# untitled.net
KiCad netlist of a schematic drawn in EAGLE
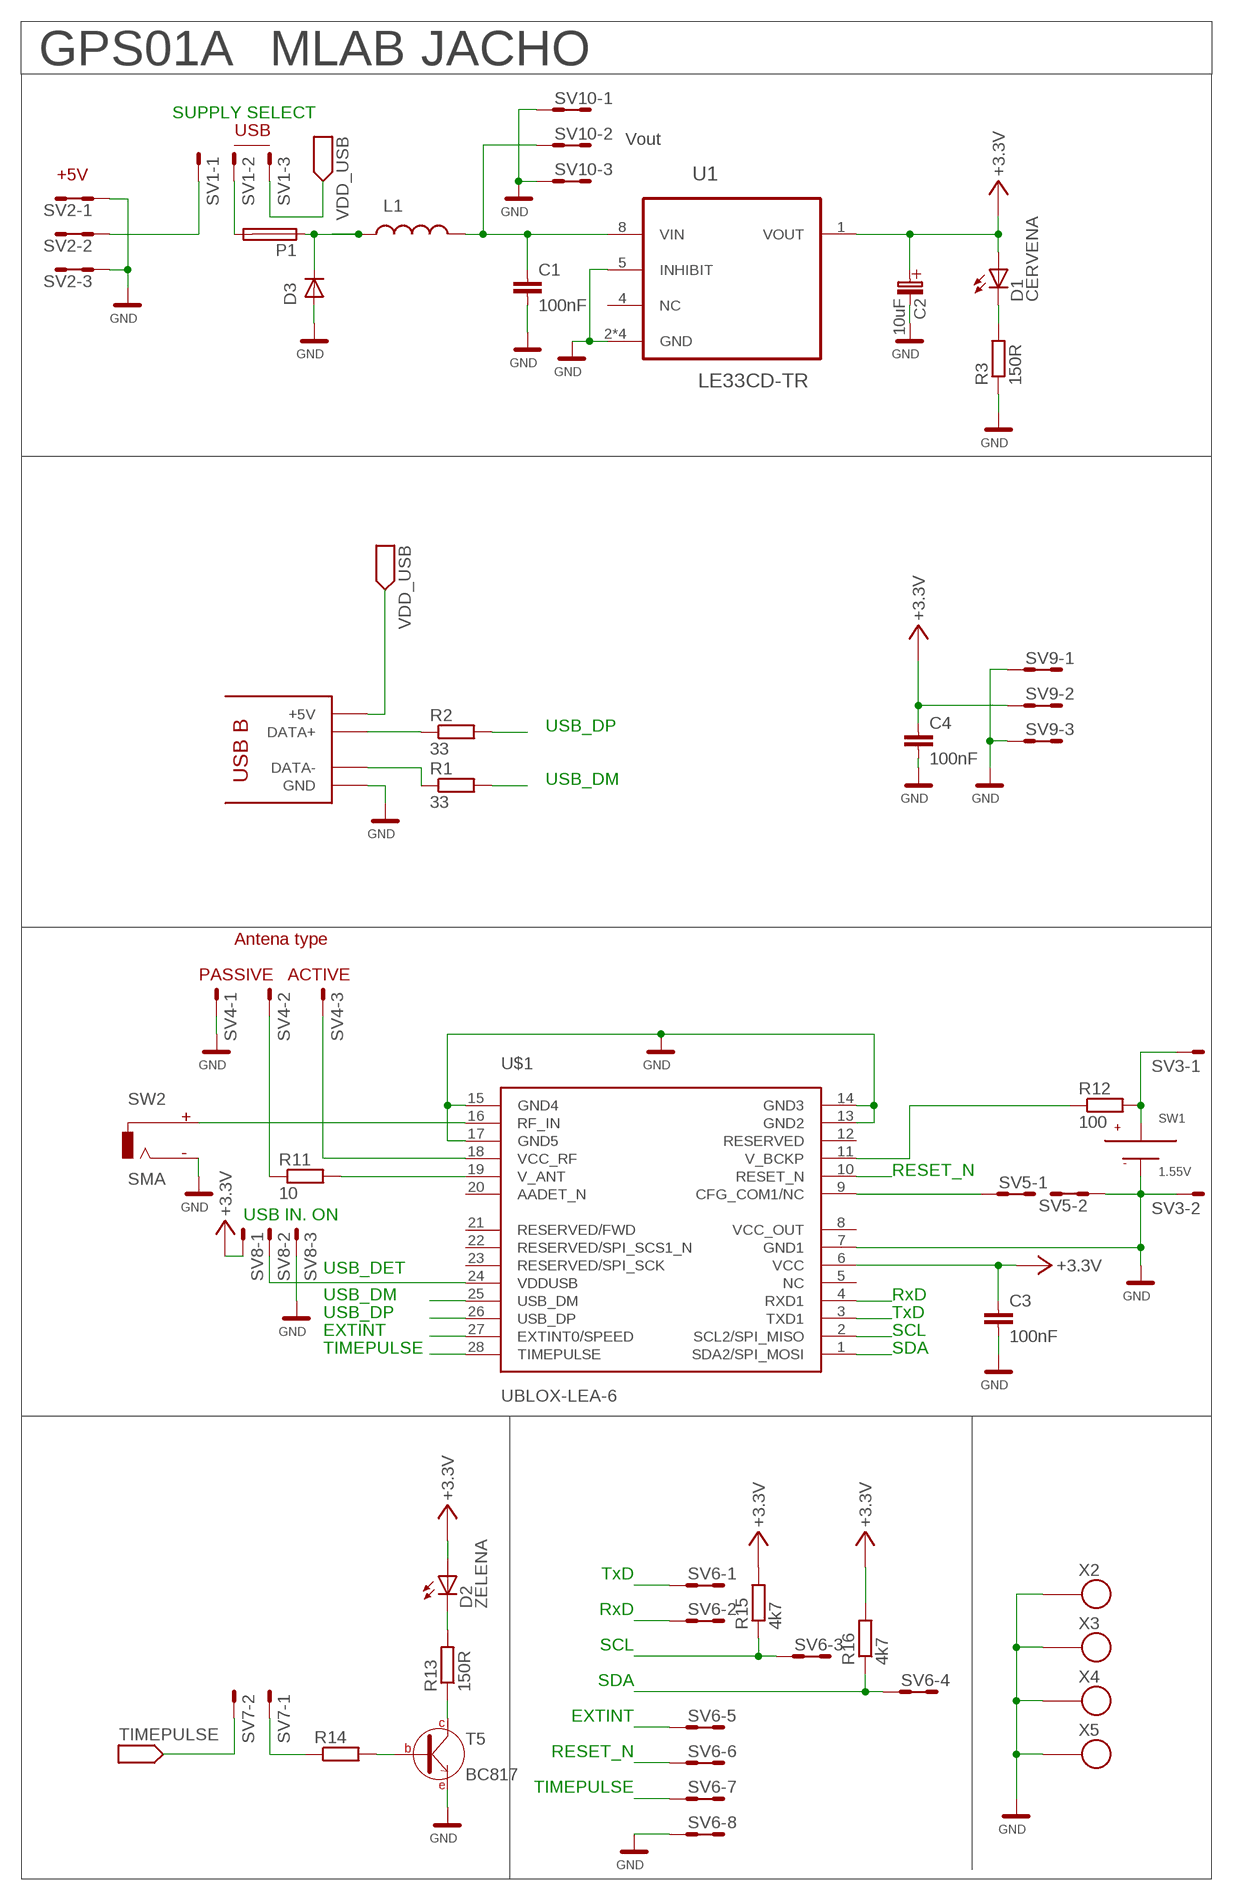
[diagram p0: schematic, sheet 1]

(export (version "E")
  (design (tool "Eeschema 10.0.6"))
  (components
    (comp (ref "C1")
      (value "100nF")
      (footprint "eagle-import:C0805")
      (libsource (lib "eagle-import") (part "C0805"))
    )
    (comp (ref "C2") (value "10uF") (footprint "eagle-import:B") (libsource (lib "eagle-import") (part "B")))
    (comp (ref "C3")
      (value "100nF")
      (footprint "eagle-import:C0805")
      (libsource (lib "eagle-import") (part "C0805"))
    )
    (comp (ref "C4")
      (value "100nF")
      (footprint "eagle-import:C0805")
      (libsource (lib "eagle-import") (part "C0805"))
    )
    (comp (ref "D1")
      (value "CERVENA")
      (footprint "eagle-import:1206")
      (libsource (lib "eagle-import") (part "LED1206"))
    )
    (comp (ref "D2")
      (value "ZELENA")
      (footprint "eagle-import:1206")
      (libsource (lib "eagle-import") (part "LED1206"))
    )
    (comp (ref "D3")
      (value "D-OB.SMA")
      (footprint "eagle-import:SMA")
      (libsource (lib "eagle-import") (part "D-OB.SMA"))
    )
    (comp (ref "L1")
      (value "L1210")
      (footprint "eagle-import:1210")
      (libsource (lib "eagle-import") (part "L1210"))
    )
    (comp (ref "P1")
      (value "POJISTKA_1812")
      (footprint "eagle-import:1812")
      (libsource (lib "eagle-import") (part "POJISTKA_1812"))
    )
    (comp (ref "R1")
      (value "33")
      (footprint "eagle-import:0805")
      (libsource (lib "eagle-import") (part "R0805"))
    )
    (comp (ref "R2")
      (value "33")
      (footprint "eagle-import:0805")
      (libsource (lib "eagle-import") (part "R0805"))
    )
    (comp (ref "R3")
      (value "150R")
      (footprint "eagle-import:0805")
      (libsource (lib "eagle-import") (part "R0805"))
    )
    (comp (ref "R11")
      (value "10")
      (footprint "eagle-import:0805")
      (libsource (lib "eagle-import") (part "R0805"))
    )
    (comp (ref "R12")
      (value "100")
      (footprint "eagle-import:0805")
      (libsource (lib "eagle-import") (part "R0805"))
    )
    (comp (ref "R13")
      (value "150R")
      (footprint "eagle-import:0805")
      (libsource (lib "eagle-import") (part "R0805"))
    )
    (comp (ref "R14")
      (value "R0805")
      (footprint "eagle-import:0805")
      (libsource (lib "eagle-import") (part "R0805"))
    )
    (comp (ref "R15")
      (value "4k7")
      (footprint "eagle-import:0805")
      (libsource (lib "eagle-import") (part "R0805"))
    )
    (comp (ref "R16")
      (value "4k7")
      (footprint "eagle-import:0805")
      (libsource (lib "eagle-import") (part "R0805"))
    )
    (comp (ref "SV1")
      (value "MA03-1")
      (footprint "eagle-import:MA03-1")
      (libsource (lib "eagle-import") (part "MA03-1"))
    )
    (comp (ref "SV2")
      (value "MA03-2")
      (footprint "eagle-import:MA03-2")
      (libsource (lib "eagle-import") (part "MA03-2"))
    )
    (comp (ref "SV3")
      (value "MA02-1")
      (footprint "eagle-import:MA02-1")
      (libsource (lib "eagle-import") (part "MA02-1"))
    )
    (comp (ref "SV4")
      (value "MA03-1")
      (footprint "eagle-import:MA03-1")
      (libsource (lib "eagle-import") (part "MA03-1"))
    )
    (comp (ref "SV5")
      (value "MA02-2")
      (footprint "eagle-import:MA02-2")
      (libsource (lib "eagle-import") (part "MA02-2"))
    )
    (comp (ref "SV6")
      (value "MA08-2")
      (footprint "eagle-import:MA08-2")
      (libsource (lib "eagle-import") (part "MA08-2"))
    )
    (comp (ref "SV7")
      (value "MA02-1")
      (footprint "eagle-import:MA02-1")
      (libsource (lib "eagle-import") (part "MA02-1"))
    )
    (comp (ref "SV8")
      (value "MA03-1")
      (footprint "eagle-import:MA03-1")
      (libsource (lib "eagle-import") (part "MA03-1"))
    )
    (comp (ref "SV9")
      (value "MA03-2")
      (footprint "eagle-import:MA03-2")
      (libsource (lib "eagle-import") (part "MA03-2"))
    )
    (comp (ref "SV10")
      (value "MA03-2")
      (footprint "eagle-import:MA03-2")
      (libsource (lib "eagle-import") (part "MA03-2"))
    )
    (comp (ref "SW1")
      (value "1.55V")
      (footprint "eagle-import:BAT6MM8")
      (libsource (lib "eagle-import") (part "BAT6MM8"))
    )
    (comp (ref "SW2")
      (value "SMA")
      (footprint "eagle-import:SMA")
      (libsource (lib "eagle-import") (part "SMA"))
    )
    (comp (ref "T5")
      (value "BC817")
      (footprint "eagle-import:SOT23")
      (libsource (lib "eagle-import") (part "BC817"))
    )
    (comp (ref "U$1")
      (value "UBLOX-LEA-6")
      (footprint "eagle-import:UBLOX-LEA-6")
      (libsource (lib "eagle-import") (part "UBLOX-LEA-6"))
    )
    (comp (ref "U1")
      (value "LE33CD-TR")
      (footprint "eagle-import:SOIC127P600X175-8N")
      (libsource (lib "eagle-import") (part "LE33CD-TR"))
    )
    (comp (ref "X1")
      (value "USB_B")
      (footprint "eagle-import:USB_B")
      (libsource (lib "eagle-import") (part "USB_B"))
    )
    (comp (ref "X2")
      (value "SROUB3M")
      (footprint "eagle-import:SROUB3M")
      (libsource (lib "eagle-import") (part "SROUB3M"))
    )
    (comp (ref "X3")
      (value "SROUB3M")
      (footprint "eagle-import:SROUB3M")
      (libsource (lib "eagle-import") (part "SROUB3M"))
    )
    (comp (ref "X4")
      (value "SROUB3M")
      (footprint "eagle-import:SROUB3M")
      (libsource (lib "eagle-import") (part "SROUB3M"))
    )
    (comp (ref "X5")
      (value "SROUB3M")
      (footprint "eagle-import:SROUB3M")
      (libsource (lib "eagle-import") (part "SROUB3M"))
    )
  )
  (nets
    (net (code "1") (name "+3.3V") (class "Default")
      (node (ref "C2") (pin "+") (pinfunction "C_EL+_+") (pintype "passive"))
      (node (ref "C3") (pin "1") (pinfunction "1_1") (pintype "passive"))
      (node (ref "C4") (pin "1") (pinfunction "1_1") (pintype "passive"))
      (node (ref "D1") (pin "A") (pinfunction "A_A") (pintype "passive"))
      (node (ref "D2") (pin "A") (pinfunction "A_A") (pintype "passive"))
      (node (ref "R15") (pin "2") (pinfunction "2_2") (pintype "passive"))
      (node (ref "R16") (pin "2") (pinfunction "2_2") (pintype "passive"))
      (node (ref "SV8") (pin "1") (pinfunction "P$1_1") (pintype "passive"))
      (node (ref "SV9") (pin "3") (pinfunction "K_3") (pintype "passive"))
      (node (ref "SV9") (pin "4") (pinfunction "K_4") (pintype "passive"))
      (node (ref "U$1") (pin "6") (pinfunction "VCC_6") (pintype "bidirectional"))
      (node (ref "U1") (pin "1") (pinfunction "VOUT_1") (pintype "output"))
    )
    (net (code "2") (name "/EXTINT") (class "Default")
      (node (ref "SV6") (pin "10") (pinfunction "K_10") (pintype "passive"))
      (node (ref "SV6") (pin "9") (pinfunction "K_9") (pintype "passive"))
      (node (ref "U$1") (pin "27") (pinfunction "EXTINT0/SPEED_27") (pintype "bidirectional"))
    )
    (net (code "3") (name "/RESET_N") (class "Default")
      (node (ref "SV6") (pin "11") (pinfunction "K_11") (pintype "passive"))
      (node (ref "SV6") (pin "12") (pinfunction "K_12") (pintype "passive"))
      (node (ref "U$1") (pin "10") (pinfunction "RESET_N_10") (pintype "bidirectional"))
    )
    (net (code "4") (name "/RXD") (class "Default")
      (node (ref "SV6") (pin "3") (pinfunction "K_3") (pintype "passive"))
      (node (ref "SV6") (pin "4") (pinfunction "K_4") (pintype "passive"))
      (node (ref "U$1") (pin "4") (pinfunction "RXD1_4") (pintype "bidirectional"))
    )
    (net (code "5") (name "/SCL") (class "Default")
      (node (ref "R15") (pin "1") (pinfunction "1_1") (pintype "passive"))
      (node (ref "SV6") (pin "5") (pinfunction "K_5") (pintype "passive"))
      (node (ref "SV6") (pin "6") (pinfunction "K_6") (pintype "passive"))
      (node (ref "U$1") (pin "2") (pinfunction "SCL2/SPI_MISO_2") (pintype "bidirectional"))
    )
    (net (code "6") (name "/SDA") (class "Default")
      (node (ref "R16") (pin "1") (pinfunction "1_1") (pintype "passive"))
      (node (ref "SV6") (pin "7") (pinfunction "K_7") (pintype "passive"))
      (node (ref "SV6") (pin "8") (pinfunction "K_8") (pintype "passive"))
      (node (ref "U$1") (pin "1") (pinfunction "SDA2/SPI_MOSI_1") (pintype "bidirectional"))
    )
    (net (code "7") (name "/TIMEPULSE") (class "Default")
      (node (ref "SV6") (pin "13") (pinfunction "K_13") (pintype "passive"))
      (node (ref "SV6") (pin "14") (pinfunction "K_14") (pintype "passive"))
      (node (ref "SV7") (pin "2") (pinfunction "P$1_2") (pintype "passive"))
      (node (ref "U$1") (pin "28") (pinfunction "TIMEPULSE_28") (pintype "bidirectional"))
    )
    (net (code "8") (name "/TXD") (class "Default")
      (node (ref "SV6") (pin "1") (pinfunction "K_1") (pintype "passive"))
      (node (ref "SV6") (pin "2") (pinfunction "K_2") (pintype "passive"))
      (node (ref "U$1") (pin "3") (pinfunction "TXD1_3") (pintype "bidirectional"))
    )
    (net (code "9") (name "/USB_DM") (class "Default")
      (node (ref "R1") (pin "2") (pinfunction "2_2") (pintype "passive"))
      (node (ref "U$1") (pin "25") (pinfunction "USB_DM_25") (pintype "bidirectional"))
    )
    (net (code "10") (name "/USB_DP") (class "Default")
      (node (ref "R2") (pin "2") (pinfunction "2_2") (pintype "passive"))
      (node (ref "U$1") (pin "26") (pinfunction "USB_DP_26") (pintype "bidirectional"))
    )
    (net (code "11") (name "/VDD_USB") (class "Default")
      (node (ref "SV1") (pin "3") (pinfunction "P$1_3") (pintype "passive"))
      (node (ref "X1") (pin "1") (pinfunction "+5V_1") (pintype "bidirectional"))
    )
    (net (code "12") (name "GND") (class "Default")
      (node (ref "C1") (pin "2") (pinfunction "2_2") (pintype "passive"))
      (node (ref "C2") (pin "-") (pinfunction "C_EL-_-") (pintype "passive"))
      (node (ref "C3") (pin "2") (pinfunction "2_2") (pintype "passive"))
      (node (ref "C4") (pin "2") (pinfunction "2_2") (pintype "passive"))
      (node (ref "D3") (pin "A") (pinfunction "A_A") (pintype "passive"))
      (node (ref "R3") (pin "1") (pinfunction "1_1") (pintype "passive"))
      (node (ref "SV10") (pin "1") (pinfunction "K_1") (pintype "passive"))
      (node (ref "SV10") (pin "2") (pinfunction "K_2") (pintype "passive"))
      (node (ref "SV10") (pin "5") (pinfunction "K_5") (pintype "passive"))
      (node (ref "SV10") (pin "6") (pinfunction "K_6") (pintype "passive"))
      (node (ref "SV2") (pin "1") (pinfunction "K_1") (pintype "passive"))
      (node (ref "SV2") (pin "2") (pinfunction "K_2") (pintype "passive"))
      (node (ref "SV2") (pin "5") (pinfunction "K_5") (pintype "passive"))
      (node (ref "SV2") (pin "6") (pinfunction "K_6") (pintype "passive"))
      (node (ref "SV3") (pin "2") (pinfunction "P$1_2") (pintype "passive"))
      (node (ref "SV4") (pin "1") (pinfunction "P$1_1") (pintype "passive"))
      (node (ref "SV5") (pin "3") (pinfunction "K_3") (pintype "passive"))
      (node (ref "SV5") (pin "4") (pinfunction "K_4") (pintype "passive"))
      (node (ref "SV6") (pin "15") (pinfunction "K_15") (pintype "passive"))
      (node (ref "SV6") (pin "16") (pinfunction "K_16") (pintype "passive"))
      (node (ref "SV8") (pin "3") (pinfunction "P$1_3") (pintype "passive"))
      (node (ref "SV9") (pin "1") (pinfunction "K_1") (pintype "passive"))
      (node (ref "SV9") (pin "2") (pinfunction "K_2") (pintype "passive"))
      (node (ref "SV9") (pin "5") (pinfunction "K_5") (pintype "passive"))
      (node (ref "SV9") (pin "6") (pinfunction "K_6") (pintype "passive"))
      (node (ref "SW1") (pin "-") (pinfunction "-_-") (pintype "passive"))
      (node (ref "SW2") (pin "-1") (pinfunction "-_-1") (pintype "passive"))
      (node (ref "SW2") (pin "-2") (pinfunction "-_-2") (pintype "passive"))
      (node (ref "SW2") (pin "-3") (pinfunction "-_-3") (pintype "passive"))
      (node (ref "SW2") (pin "-4") (pinfunction "-_-4") (pintype "passive"))
      (node (ref "T5") (pin "2") (pinfunction "E_2") (pintype "passive"))
      (node (ref "U$1") (pin "13") (pinfunction "GND2_13") (pintype "bidirectional"))
      (node (ref "U$1") (pin "14") (pinfunction "GND3_14") (pintype "bidirectional"))
      (node (ref "U$1") (pin "15") (pinfunction "GND4_15") (pintype "bidirectional"))
      (node (ref "U$1") (pin "17") (pinfunction "GND5_17") (pintype "bidirectional"))
      (node (ref "U$1") (pin "7") (pinfunction "GND1_7") (pintype "bidirectional"))
      (node (ref "U1") (pin "2") (pinfunction "GND_2") (pintype "passive"))
      (node (ref "U1") (pin "3") (pinfunction "GND_3") (pintype "passive"))
      (node (ref "U1") (pin "5") (pinfunction "INHIBIT_5") (pintype "passive"))
      (node (ref "U1") (pin "6") (pinfunction "GND_6") (pintype "passive"))
      (node (ref "U1") (pin "7") (pinfunction "GND_7") (pintype "passive"))
      (node (ref "X1") (pin "4") (pinfunction "GND_4") (pintype "bidirectional"))
      (node (ref "X1") (pin "GND") (pinfunction "GND_GND") (pintype "bidirectional"))
      (node (ref "X1") (pin "GND2") (pinfunction "GND_GND2") (pintype "bidirectional"))
      (node (ref "X2") (pin "P$1") (pinfunction "P$1_P$1") (pintype "bidirectional"))
      (node (ref "X3") (pin "P$1") (pinfunction "P$1_P$1") (pintype "bidirectional"))
      (node (ref "X4") (pin "P$1") (pinfunction "P$1_P$1") (pintype "bidirectional"))
      (node (ref "X5") (pin "P$1") (pinfunction "P$1_P$1") (pintype "bidirectional"))
    )
    (net (code "13") (name "Net-(D1-C)") (class "Default")
      (node (ref "D1") (pin "K") (pinfunction "C_K") (pintype "passive"))
      (node (ref "R3") (pin "2") (pinfunction "2_2") (pintype "passive"))
    )
    (net (code "14") (name "Net-(D2-C)") (class "Default")
      (node (ref "D2") (pin "K") (pinfunction "C_K") (pintype "passive"))
      (node (ref "R13") (pin "2") (pinfunction "2_2") (pintype "passive"))
    )
    (net (code "15") (name "Net-(D3-C)") (class "Default")
      (node (ref "D3") (pin "K") (pinfunction "C_K") (pintype "passive"))
      (node (ref "L1") (pin "P$1") (pinfunction "1_P$1") (pintype "passive"))
      (node (ref "P1") (pin "1") (pinfunction "1_1") (pintype "passive"))
    )
    (net (code "16") (name "Net-(L1-2)") (class "Default")
      (node (ref "C1") (pin "1") (pinfunction "1_1") (pintype "passive"))
      (node (ref "L1") (pin "P$2") (pinfunction "2_P$2") (pintype "passive"))
      (node (ref "SV10") (pin "3") (pinfunction "K_3") (pintype "passive"))
      (node (ref "SV10") (pin "4") (pinfunction "K_4") (pintype "passive"))
      (node (ref "U1") (pin "8") (pinfunction "VIN_8") (pintype "power_in"))
    )
    (net (code "17") (name "Net-(SV1A-P$1)") (class "Default")
      (node (ref "SV1") (pin "1") (pinfunction "P$1_1") (pintype "passive"))
      (node (ref "SV2") (pin "3") (pinfunction "K_3") (pintype "passive"))
      (node (ref "SV2") (pin "4") (pinfunction "K_4") (pintype "passive"))
    )
    (net (code "18") (name "Net-(SV1B-P$1)") (class "Default")
      (node (ref "P1") (pin "2") (pinfunction "2_2") (pintype "passive"))
      (node (ref "SV1") (pin "2") (pinfunction "P$1_2") (pintype "passive"))
    )
    (net (code "19") (name "Net-(SV3A-P$1)") (class "Default")
      (node (ref "R12") (pin "2") (pinfunction "2_2") (pintype "passive"))
      (node (ref "SV3") (pin "1") (pinfunction "P$1_1") (pintype "passive"))
      (node (ref "SW1") (pin "1+") (pinfunction "+_1+") (pintype "passive"))
      (node (ref "SW1") (pin "2+") (pinfunction "+_2+") (pintype "passive"))
    )
    (net (code "20") (name "Net-(SV4B-P$1)") (class "Default")
      (node (ref "R11") (pin "1") (pinfunction "1_1") (pintype "passive"))
      (node (ref "SV4") (pin "2") (pinfunction "P$1_2") (pintype "passive"))
    )
    (net (code "21") (name "Net-(SV4C-P$1)") (class "Default")
      (node (ref "SV4") (pin "3") (pinfunction "P$1_3") (pintype "passive"))
      (node (ref "U$1") (pin "18") (pinfunction "VCC_RF_18") (pintype "bidirectional"))
    )
    (net (code "22") (name "Net-(SV7A-P$1)") (class "Default")
      (node (ref "R14") (pin "1") (pinfunction "1_1") (pintype "passive"))
      (node (ref "SV7") (pin "1") (pinfunction "P$1_1") (pintype "passive"))
    )
    (net (code "23") (name "Net-(SV8B-P$1)") (class "Default")
      (node (ref "SV8") (pin "2") (pinfunction "P$1_2") (pintype "passive"))
      (node (ref "U$1") (pin "24") (pinfunction "VDDUSB_24") (pintype "bidirectional"))
    )
    (net (code "24") (name "Net-(T5-B)") (class "Default")
      (node (ref "R14") (pin "2") (pinfunction "2_2") (pintype "passive"))
      (node (ref "T5") (pin "1") (pinfunction "B_1") (pintype "passive"))
    )
    (net (code "25") (name "Net-(T5-C)") (class "Default")
      (node (ref "R13") (pin "1") (pinfunction "1_1") (pintype "passive"))
      (node (ref "T5") (pin "3") (pinfunction "C_3") (pintype "passive"))
    )
    (net (code "26") (name "Net-(U$1-CFG_COM1{slash}NC)") (class "Default")
      (node (ref "SV5") (pin "1") (pinfunction "K_1") (pintype "passive"))
      (node (ref "SV5") (pin "2") (pinfunction "K_2") (pintype "passive"))
      (node (ref "U$1") (pin "9") (pinfunction "CFG_COM1/NC_9") (pintype "bidirectional"))
    )
    (net (code "27") (name "Net-(U$1-RF_IN)") (class "Default")
      (node (ref "SW2") (pin "+") (pinfunction "+_+") (pintype "passive"))
      (node (ref "U$1") (pin "16") (pinfunction "RF_IN_16") (pintype "bidirectional"))
    )
    (net (code "28") (name "Net-(U$1-V_ANT)") (class "Default")
      (node (ref "R11") (pin "2") (pinfunction "2_2") (pintype "passive"))
      (node (ref "U$1") (pin "19") (pinfunction "V_ANT_19") (pintype "bidirectional"))
    )
    (net (code "29") (name "Net-(U$1-V_BCKP)") (class "Default")
      (node (ref "R12") (pin "1") (pinfunction "1_1") (pintype "passive"))
      (node (ref "U$1") (pin "11") (pinfunction "V_BCKP_11") (pintype "bidirectional"))
    )
    (net (code "30") (name "Net-(X1-DATA+)") (class "Default")
      (node (ref "R2") (pin "1") (pinfunction "1_1") (pintype "passive"))
      (node (ref "X1") (pin "3") (pinfunction "DATA+_3") (pintype "bidirectional"))
    )
    (net (code "31") (name "Net-(X1-DATA-)") (class "Default")
      (node (ref "R1") (pin "1") (pinfunction "1_1") (pintype "passive"))
      (node (ref "X1") (pin "2") (pinfunction "DATA-_2") (pintype "bidirectional"))
    )
    (net (code "32") (name "unconnected-(U$1-AADET_N-Pad20)") (class "Default")
      (node (ref "U$1") (pin "20") (pinfunction "AADET_N_20") (pintype "bidirectional"))
    )
    (net (code "33") (name "unconnected-(U$1-NC-Pad5)") (class "Default")
      (node (ref "U$1") (pin "5") (pinfunction "NC_5") (pintype "bidirectional"))
    )
    (net (code "34") (name "unconnected-(U$1-RESERVED-Pad12)") (class "Default")
      (node (ref "U$1") (pin "12") (pinfunction "RESERVED_12") (pintype "bidirectional"))
    )
    (net (code "35") (name "unconnected-(U$1-RESERVED{slash}FWD-Pad21)") (class "Default")
      (node (ref "U$1") (pin "21") (pinfunction "RESERVED/FWD_21") (pintype "bidirectional"))
    )
    (net (code "36") (name "unconnected-(U$1-RESERVED{slash}SPI_SCK-Pad23)") (class "Default")
      (node (ref "U$1") (pin "23") (pinfunction "RESERVED/SPI_SCK_23") (pintype "bidirectional"))
    )
    (net (code "37") (name "unconnected-(U$1-RESERVED{slash}SPI_SCS1_N-Pad22)") (class "Default")
      (node (ref "U$1") (pin "22") (pinfunction "RESERVED/SPI_SCS1_N_22") (pintype "bidirectional"))
    )
    (net (code "38") (name "unconnected-(U$1-VCC_OUT-Pad8)") (class "Default")
      (node (ref "U$1") (pin "8") (pinfunction "VCC_OUT_8") (pintype "bidirectional"))
    )
    (net (code "39") (name "unconnected-(U1-NC-Pad4)") (class "Default")
      (node (ref "U1") (pin "4") (pinfunction "NC_4") (pintype "no_connect"))
    )
  )
)
